# kicker_v20.net
KiCad netlist of a schematic drawn in EAGLE
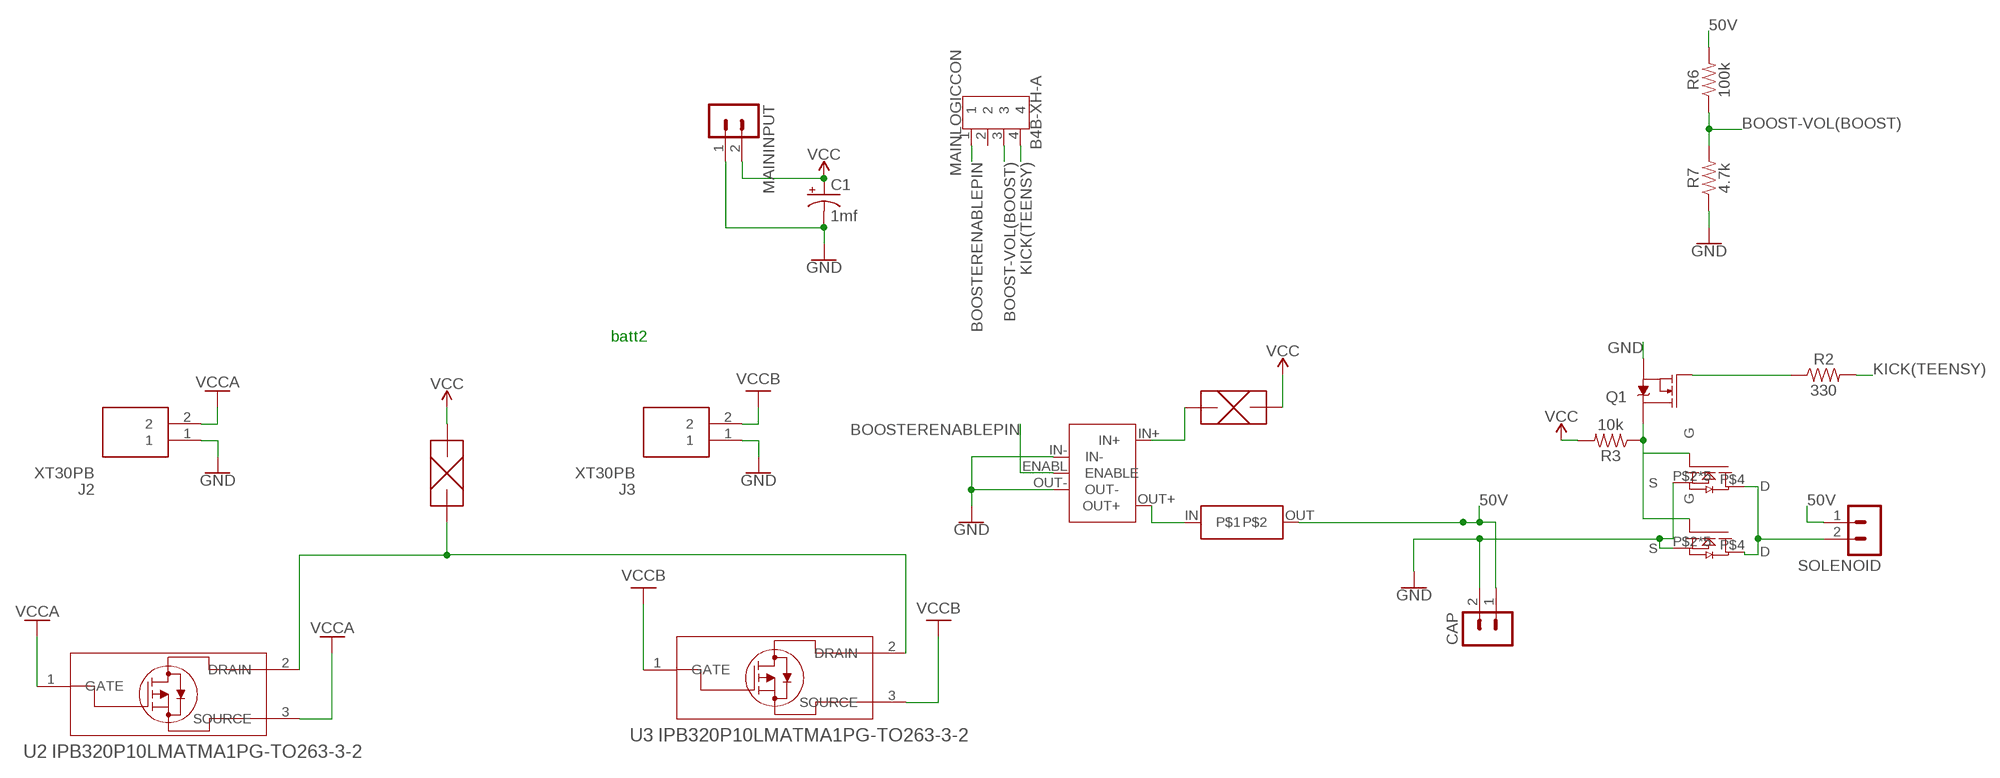
[diagram p0: schematic, sheet 1]

(export (version "E")
  (design (tool "Eeschema 10.0.6"))
  (components
    (comp (ref "C1")
      (value "1mf")
      (footprint "eagle-import:CPOL-RADIAL-5MM-10MM-KIT")
      (libsource (lib "eagle-import") (part "1000UF-RADIAL-5MM-35V-20%-KIT"))
    )
    (comp (ref "CAP")
      (value "B2P-VH-FB-B")
      (footprint "eagle-import:B2P-VH-FB-B")
      (libsource (lib "eagle-import") (part "B2P-VH-FB-B"))
    )
    (comp (ref "J2")
      (value "XT30PB")
      (footprint "eagle-import:XT30PB")
      (libsource (lib "eagle-import") (part "XT30PB"))
    )
    (comp (ref "J3")
      (value "XT30PB")
      (footprint "eagle-import:XT30PB")
      (libsource (lib "eagle-import") (part "XT30PB"))
    )
    (comp (ref "MAININPUT")
      (value "B2P-VH-B")
      (footprint "eagle-import:B2P-VH")
      (libsource (lib "eagle-import") (part "B2P-VH-B"))
    )
    (comp (ref "MAINLOGICCON")
      (value "B4B-XH-A")
      (footprint "eagle-import:B4B-XH-A")
      (fields (field (name "MANUFACTURER") "JST Sales America Inc.") (field (name "MPN") "B4B-XH-A(LF)(SN)"))
      (libsource (lib "eagle-import") (part "B4B-XH-A"))
    )
    (comp (ref "Q1")
      (value "5.8A/30V/35mΩ")
      (footprint "eagle-import:SOT23-3")
      (libsource (lib "eagle-import") (part "MOSFET-NCH-AO3404A"))
    )
    (comp (ref "R2")
      (value "330")
      (footprint "eagle-import:0603")
      (libsource (lib "eagle-import") (part "330KOHM-0603-1/10W-1%"))
    )
    (comp (ref "R3")
      (value "10k")
      (footprint "eagle-import:0603")
      (libsource (lib "eagle-import") (part "10KOHM-0603-1/10W-1%"))
    )
    (comp (ref "R6")
      (value "100k")
      (footprint "eagle-import:0603")
      (libsource (lib "eagle-import") (part "10KOHM-0603-1/10W-1%"))
    )
    (comp (ref "R7")
      (value "4.7k")
      (footprint "eagle-import:0603")
      (libsource (lib "eagle-import") (part "10KOHM-0603-1/10W-1%"))
    )
    (comp (ref "SOLENOID")
      (value "B2P-VH-FB-B")
      (footprint "eagle-import:B2P-VH-FB-B")
      (libsource (lib "eagle-import") (part "B2P-VH-FB-B"))
    )
    (comp (ref "U$1")
      (value "N-CH_D2PAK-7P")
      (footprint "eagle-import:D2PAK-7P")
      (libsource (lib "eagle-import") (part "N-CH_D2PAK-7P"))
    )
    (comp (ref "U$2")
      (value "N-CH_D2PAK-7P")
      (footprint "eagle-import:D2PAK-7P")
      (libsource (lib "eagle-import") (part "N-CH_D2PAK-7P"))
    )
    (comp (ref "U$3")
      (value "HPRE")
      (footprint "eagle-import:HPRE")
      (libsource (lib "eagle-import") (part "HPRE"))
    )
    (comp (ref "U$4")
      (value "VOLTAGEBOOSTER")
      (footprint "eagle-import:VOLTAGEBOOSTER")
      (libsource (lib "eagle-import") (part "VOLTAGEBOOSTER"))
    )
    (comp (ref "U$5")
      (value "FUSE-HORIZONTAL")
      (footprint "eagle-import:MINI-RIGHT")
      (libsource (lib "eagle-import") (part "FUSE-HORIZONTAL"))
    )
    (comp (ref "U$6")
      (value "FUSE-HORIZONTAL")
      (footprint "eagle-import:MINI-RIGHT")
      (libsource (lib "eagle-import") (part "FUSE-HORIZONTAL"))
    )
    (comp (ref "U2")
      (value "IPB320P10LMATMA1PG-TO263-3-2")
      (footprint "eagle-import:PG-TO263-3-2")
      (fields
        (field (name "MANUFACTURER_PART_NUMBER") "IPB320P10LMATMA1")
        (field (name "COPYRIGHT") "Copyright (C) 2023 Ultra Librarian. All rights reserved.")
      )
      (libsource (lib "eagle-import") (part "IPB320P10LMATMA1PG-TO263-3-2"))
    )
    (comp (ref "U3")
      (value "IPB320P10LMATMA1PG-TO263-3-2")
      (footprint "eagle-import:PG-TO263-3-2")
      (fields
        (field (name "MANUFACTURER_PART_NUMBER") "IPB320P10LMATMA1")
        (field (name "COPYRIGHT") "Copyright (C) 2023 Ultra Librarian. All rights reserved.")
      )
      (libsource (lib "eagle-import") (part "IPB320P10LMATMA1PG-TO263-3-2"))
    )
  )
  (nets
    (net (code "1") (name "/50V") (class "Default")
      (node (ref "CAP") (pin "1") (pinfunction "1_1") (pintype "passive"))
      (node (ref "R6") (pin "2") (pinfunction "2_2") (pintype "passive"))
      (node (ref "SOLENOID") (pin "1") (pinfunction "1_1") (pintype "passive"))
      (node (ref "U$3") (pin "OUT") (pinfunction "P$2_OUT") (pintype "bidirectional"))
    )
    (net (code "2") (name "/BOOST-VOL(BOOST)") (class "Default")
      (node (ref "MAINLOGICCON") (pin "3") (pinfunction "3_3") (pintype "bidirectional"))
      (node (ref "R6") (pin "1") (pinfunction "1_1") (pintype "passive"))
      (node (ref "R7") (pin "2") (pinfunction "2_2") (pintype "passive"))
    )
    (net (code "3") (name "/BOOSTERENABLEPIN") (class "Default")
      (node (ref "MAINLOGICCON") (pin "1") (pinfunction "1_1") (pintype "bidirectional"))
      (node (ref "U$4") (pin "ENABL") (pinfunction "ENABLE_ENABL") (pintype "bidirectional"))
    )
    (net (code "4") (name "/KICK(TEENSY)") (class "Default")
      (node (ref "MAINLOGICCON") (pin "4") (pinfunction "4_4") (pintype "bidirectional"))
      (node (ref "R2") (pin "2") (pinfunction "2_2") (pintype "passive"))
    )
    (net (code "5") (name "GND") (class "Default")
      (node (ref "C1") (pin "-") (pinfunction "-_-") (pintype "passive"))
      (node (ref "CAP") (pin "2") (pinfunction "2_2") (pintype "passive"))
      (node (ref "J2") (pin "1") (pinfunction "1_1") (pintype "bidirectional"))
      (node (ref "J3") (pin "1") (pinfunction "1_1") (pintype "bidirectional"))
      (node (ref "MAININPUT") (pin "1") (pinfunction "1_1") (pintype "passive"))
      (node (ref "Q1") (pin "2") (pinfunction "S_2") (pintype "bidirectional"))
      (node (ref "R7") (pin "1") (pinfunction "1_1") (pintype "passive"))
      (node (ref "U$1") (pin "P$2") (pinfunction "S_P$2") (pintype "bidirectional"))
      (node (ref "U$1") (pin "P$3") (pinfunction "S_P$3") (pintype "bidirectional"))
      (node (ref "U$1") (pin "P$5") (pinfunction "S_P$5") (pintype "bidirectional"))
      (node (ref "U$1") (pin "P$6") (pinfunction "S_P$6") (pintype "bidirectional"))
      (node (ref "U$1") (pin "P$7") (pinfunction "S_P$7") (pintype "bidirectional"))
      (node (ref "U$2") (pin "P$2") (pinfunction "S_P$2") (pintype "bidirectional"))
      (node (ref "U$2") (pin "P$3") (pinfunction "S_P$3") (pintype "bidirectional"))
      (node (ref "U$2") (pin "P$5") (pinfunction "S_P$5") (pintype "bidirectional"))
      (node (ref "U$2") (pin "P$6") (pinfunction "S_P$6") (pintype "bidirectional"))
      (node (ref "U$2") (pin "P$7") (pinfunction "S_P$7") (pintype "bidirectional"))
      (node (ref "U$4") (pin "IN-") (pinfunction "IN-_IN-") (pintype "bidirectional"))
      (node (ref "U$4") (pin "OUT-") (pinfunction "OUT-_OUT-") (pintype "bidirectional"))
    )
    (net (code "6") (name "Net-(Q1-D)") (class "Default")
      (node (ref "Q1") (pin "3") (pinfunction "D_3") (pintype "bidirectional"))
      (node (ref "R3") (pin "1") (pinfunction "1_1") (pintype "passive"))
      (node (ref "U$1") (pin "P$1") (pinfunction "G_P$1") (pintype "bidirectional"))
      (node (ref "U$2") (pin "P$1") (pinfunction "G_P$1") (pintype "bidirectional"))
    )
    (net (code "7") (name "Net-(Q1-G)") (class "Default")
      (node (ref "Q1") (pin "1") (pinfunction "G_1") (pintype "bidirectional"))
      (node (ref "R2") (pin "1") (pinfunction "1_1") (pintype "passive"))
    )
    (net (code "8") (name "Net-(U$1-D)") (class "Default")
      (node (ref "SOLENOID") (pin "2") (pinfunction "2_2") (pintype "passive"))
      (node (ref "U$1") (pin "P$4") (pinfunction "D_P$4") (pintype "bidirectional"))
      (node (ref "U$2") (pin "P$4") (pinfunction "D_P$4") (pintype "bidirectional"))
    )
    (net (code "9") (name "Net-(U$3-P$1)") (class "Default")
      (node (ref "U$3") (pin "IN") (pinfunction "P$1_IN") (pintype "bidirectional"))
      (node (ref "U$4") (pin "OUT+") (pinfunction "OUT+_OUT+") (pintype "bidirectional"))
    )
    (net (code "10") (name "Net-(U$4-PadIN+)") (class "Default")
      (node (ref "U$4") (pin "IN+") (pinfunction "IN+_IN+") (pintype "bidirectional"))
      (node (ref "U$5") (pin "P$1") (pinfunction "P$1_P$1") (pintype "bidirectional"))
      (node (ref "U$5") (pin "P$3") (pinfunction "P$1_P$3") (pintype "bidirectional"))
    )
    (net (code "11") (name "Net-(U2-DRAIN)") (class "Default")
      (node (ref "U$6") (pin "P$1") (pinfunction "P$1_P$1") (pintype "bidirectional"))
      (node (ref "U$6") (pin "P$3") (pinfunction "P$1_P$3") (pintype "bidirectional"))
      (node (ref "U2") (pin "2") (pinfunction "DRAIN_2") (pintype "passive"))
      (node (ref "U3") (pin "2") (pinfunction "DRAIN_2") (pintype "passive"))
    )
    (net (code "12") (name "VCC") (class "Default")
      (node (ref "C1") (pin "+") (pinfunction "+_+") (pintype "passive"))
      (node (ref "MAININPUT") (pin "2") (pinfunction "2_2") (pintype "passive"))
      (node (ref "R3") (pin "2") (pinfunction "2_2") (pintype "passive"))
      (node (ref "U$5") (pin "P$2") (pinfunction "P$2_P$2") (pintype "bidirectional"))
      (node (ref "U$5") (pin "P$4") (pinfunction "P$2_P$4") (pintype "bidirectional"))
      (node (ref "U$6") (pin "P$2") (pinfunction "P$2_P$2") (pintype "bidirectional"))
      (node (ref "U$6") (pin "P$4") (pinfunction "P$2_P$4") (pintype "bidirectional"))
    )
    (net (code "13") (name "VCCA") (class "Default")
      (node (ref "J2") (pin "2") (pinfunction "2_2") (pintype "bidirectional"))
      (node (ref "U2") (pin "1") (pinfunction "GATE_1") (pintype "passive"))
      (node (ref "U2") (pin "3") (pinfunction "SOURCE_3") (pintype "passive"))
    )
    (net (code "14") (name "VCCB") (class "Default")
      (node (ref "J3") (pin "2") (pinfunction "2_2") (pintype "bidirectional"))
      (node (ref "U3") (pin "1") (pinfunction "GATE_1") (pintype "passive"))
      (node (ref "U3") (pin "3") (pinfunction "SOURCE_3") (pintype "passive"))
    )
    (net (code "15") (name "unconnected-(MAINLOGICCON-Pad2)") (class "Default")
      (node (ref "MAINLOGICCON") (pin "2") (pinfunction "2_2") (pintype "bidirectional"))
    )
  )
)
